# CarACESP32.net
KiCad netlist of a schematic drawn in Altium Designer
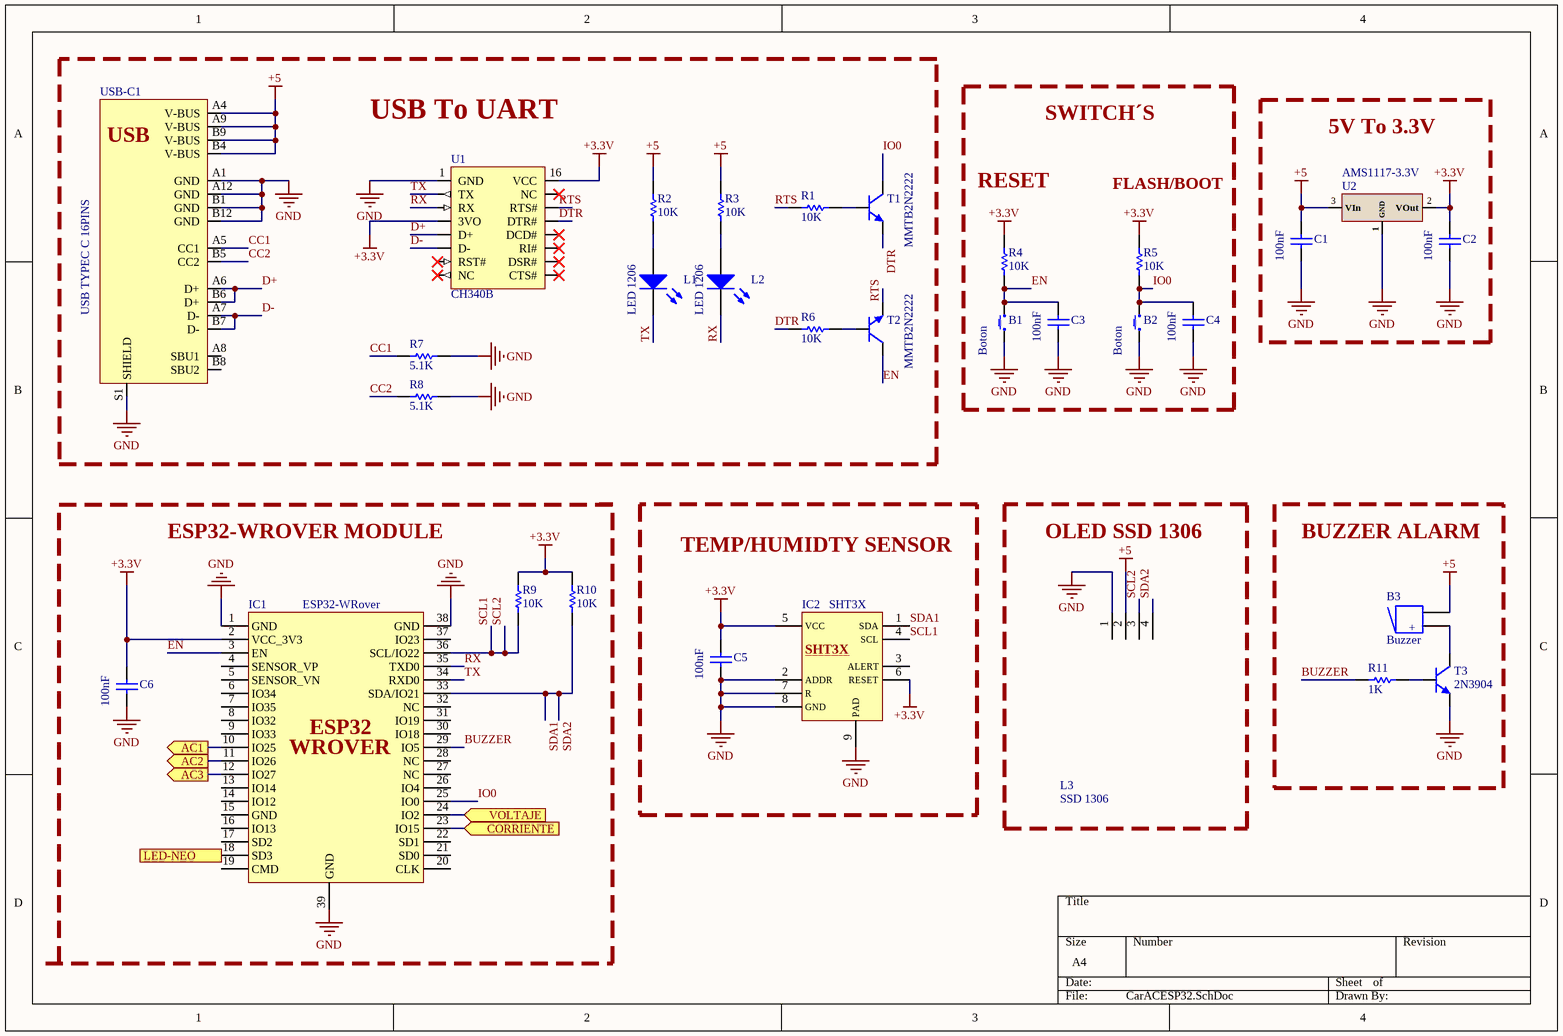
[diagram p0: CarACESP32.SchDoc]

(export (version "E")
  (design (tool "Eeschema 10.0.6"))
  (components
    (comp (ref "B1")
      (value "Boton")
      (footprint "Push Boton 2P C")
      (description "Micro Push TH")
      (libsource (lib "Switch & Relays FAE") (part "Push Boton 2 Pin TH"))
    )
    (comp (ref "B2")
      (value "Boton")
      (footprint "Push Boton 2P C")
      (description "Micro Push TH")
      (libsource (lib "Switch & Relays FAE") (part "Push Boton 2 Pin TH"))
    )
    (comp (ref "B3")
      (value "Buzzer")
      (footprint "Buzzer")
      (description "Active Sound")
      (libsource (lib "Mi Libreria") (part "Buzzer"))
    )
    (comp (ref "C1")
      (value "100nF")
      (footprint "Capacitor 1206")
      (description "Capacitor cerámico 1206 SMD")
      (libsource (lib "Mi Libreria") (part "Capacitor 1206"))
    )
    (comp (ref "C2")
      (value "100nF")
      (footprint "Capacitor 1206")
      (description "Capacitor cerámico 1206 SMD")
      (libsource (lib "Mi Libreria") (part "Capacitor 1206"))
    )
    (comp (ref "C3")
      (value "100nF")
      (footprint "Capacitor 1206")
      (description "Capacitor cerámico 1206 SMD")
      (libsource (lib "Mi Libreria") (part "Capacitor 1206"))
    )
    (comp (ref "C4")
      (value "100nF")
      (footprint "Capacitor 1206")
      (description "Capacitor cerámico 1206 SMD")
      (libsource (lib "Mi Libreria") (part "Capacitor 1206"))
    )
    (comp (ref "C5")
      (value "100nF")
      (footprint "Capacitor 1206")
      (description "Capacitor cerámico 1206 SMD")
      (libsource (lib "Mi Libreria") (part "Capacitor 1206"))
    )
    (comp (ref "C6")
      (value "100nF")
      (footprint "Capacitor 1206")
      (description "Capacitor cerámico 1206 SMD")
      (libsource (lib "Mi Libreria") (part "Capacitor 1206"))
    )
    (comp (ref "IC1")
      (value "ESP32-WRover")
      (footprint "ESP32-WROVER-B")
      (description "ESP32-WRover 39Pins")
      (libsource (lib "MyLabrary") (part "ESP32-WRover"))
    )
    (comp (ref "IC2") (value "SHT3X") (footprint "DFN-8_DD") (libsource (lib "MyLabrary") (part "SHT3X")))
    (comp (ref "L1")
      (value "LED 1206")
      (footprint "LED 1206 G")
      (description "LED SMD 1206")
      (libsource (lib "Led & Displays") (part "LED 1206"))
    )
    (comp (ref "L2")
      (value "LED 1206")
      (footprint "LED 1206 R")
      (description "LED SMD 1206")
      (libsource (lib "Led & Displays") (part "LED 1206"))
    )
    (comp (ref "L3")
      (value "SSD 1306")
      (footprint "OLEDSSD1306")
      (description "Pantalla OLED 124x64")
      (libsource (lib "MyLabrary") (part "SSD 1306"))
    )
    (comp (ref "R1")
      (value "10K")
      (footprint "Resistencia 1206")
      (description "Resistencia SMD 1206")
      (libsource (lib "Mi Libreria") (part "Resistencia SMD 1206"))
    )
    (comp (ref "R2")
      (value "10K")
      (footprint "Resistencia 1206")
      (description "Resistencia SMD 1206")
      (libsource (lib "Mi Libreria") (part "Resistencia SMD 1206"))
    )
    (comp (ref "R3")
      (value "10K")
      (footprint "Resistencia 1206")
      (description "Resistencia SMD 1206")
      (libsource (lib "Mi Libreria") (part "Resistencia SMD 1206"))
    )
    (comp (ref "R4")
      (value "10K")
      (footprint "Resistencia 1206")
      (description "Resistencia SMD 1206")
      (libsource (lib "Mi Libreria") (part "Resistencia SMD 1206"))
    )
    (comp (ref "R5")
      (value "10K")
      (footprint "Resistencia 1206")
      (description "Resistencia SMD 1206")
      (libsource (lib "Mi Libreria") (part "Resistencia SMD 1206"))
    )
    (comp (ref "R6")
      (value "10K")
      (footprint "Resistencia 1206")
      (description "Resistencia SMD 1206")
      (libsource (lib "Mi Libreria") (part "Resistencia SMD 1206"))
    )
    (comp (ref "R7")
      (value "5.1K")
      (footprint "Resistencia 1206")
      (description "Resistencia SMD 1206")
      (libsource (lib "Mi Libreria") (part "Resistencia SMD 1206"))
    )
    (comp (ref "R8")
      (value "5.1K")
      (footprint "Resistencia 1206")
      (description "Resistencia SMD 1206")
      (libsource (lib "Mi Libreria") (part "Resistencia SMD 1206"))
    )
    (comp (ref "R9")
      (value "10K")
      (footprint "Resistencia 1206")
      (description "Resistencia SMD 1206")
      (libsource (lib "Mi Libreria") (part "Resistencia SMD 1206"))
    )
    (comp (ref "R10")
      (value "10K")
      (footprint "Resistencia 1206")
      (description "Resistencia SMD 1206")
      (libsource (lib "Mi Libreria") (part "Resistencia SMD 1206"))
    )
    (comp (ref "R11")
      (value "1K")
      (footprint "Resistencia 1206")
      (description "Resistencia SMD 1206")
      (libsource (lib "Mi Libreria") (part "Resistencia SMD 1206"))
    )
    (comp (ref "T1")
      (value "MMTB2N2222")
      (footprint "SOT23_M")
      (libsource (lib "MyLabrary") (part "MMBT2N2222A"))
    )
    (comp (ref "T2")
      (value "MMTB2N2222")
      (footprint "SOT23_M")
      (libsource (lib "MyLabrary") (part "MMBT2N2222A"))
    )
    (comp (ref "T3") (value "2N3904") (footprint "NewTO-92A") (libsource (lib "MyLabrary") (part "2N3904")))
    (comp (ref "U1")
      (value "CH340B")
      (footprint "SOIC 16")
      (description "USB-Serial Converter")
      (libsource (lib "MyLabrary") (part "CH340B"))
    )
    (comp (ref "U2")
      (value "AMS1117-3.3V")
      (footprint "SOT 223")
      (description "Regulador Lineal de Voltaje")
      (libsource (lib "Mi Libreria") (part "AMS1117"))
    )
    (comp (ref "USB-C1")
      (value "USB TYPEC C 16PINS")
      (footprint "USB-TYPE_C-16")
      (description "USB Type C 16 Pins")
      (libsource (lib "MyLabrary") (part "USB TYPEC C 16PINS"))
    )
  )
  (nets
    (net (code "1") (name "+3.3V") (class "Default")
      (node (ref "C2") (pin "2") (pinfunction "2_2") (pintype "passive"))
      (node (ref "C5") (pin "2") (pinfunction "2_2") (pintype "passive"))
      (node (ref "C6") (pin "2") (pinfunction "2_2") (pintype "passive"))
      (node (ref "IC1") (pin "2") (pinfunction "VCC_3V3_2") (pintype "passive"))
      (node (ref "IC2") (pin "5") (pinfunction "VCC_5") (pintype "passive"))
      (node (ref "IC2") (pin "6") (pinfunction "RESET_6") (pintype "passive"))
      (node (ref "R10") (pin "2") (pinfunction "B_2") (pintype "passive"))
      (node (ref "R4") (pin "2") (pinfunction "B_2") (pintype "passive"))
      (node (ref "R5") (pin "2") (pinfunction "B_2") (pintype "passive"))
      (node (ref "R9") (pin "2") (pinfunction "B_2") (pintype "passive"))
      (node (ref "U1") (pin "16") (pinfunction "VCC_16") (pintype "passive"))
      (node (ref "U1") (pin "4") (pinfunction "3VO_4") (pintype "passive"))
      (node (ref "U2") (pin "2") (pinfunction "VOut_2") (pintype "passive"))
    )
    (net (code "2") (name "+5") (class "Default")
      (node (ref "B3") (pin "2") (pinfunction "2_2") (pintype "passive"))
      (node (ref "C1") (pin "2") (pinfunction "2_2") (pintype "passive"))
      (node (ref "L3") (pin "2") (pinfunction "2_2") (pintype "passive"))
      (node (ref "R2") (pin "2") (pinfunction "B_2") (pintype "passive"))
      (node (ref "R3") (pin "2") (pinfunction "B_2") (pintype "passive"))
      (node (ref "U2") (pin "3") (pinfunction "VIn_3") (pintype "passive"))
      (node (ref "USB-C1") (pin "A4") (pinfunction "V-BUS_A4") (pintype "passive"))
      (node (ref "USB-C1") (pin "A9") (pinfunction "V-BUS_A9") (pintype "passive"))
      (node (ref "USB-C1") (pin "B4") (pinfunction "V-BUS_B4") (pintype "passive"))
      (node (ref "USB-C1") (pin "B9") (pinfunction "V-BUS_B9") (pintype "passive"))
    )
    (net (code "3") (name "/AC1") (class "Default")
      (node (ref "IC1") (pin "10") (pinfunction "IO25_10") (pintype "passive"))
    )
    (net (code "4") (name "/AC2") (class "Default")
      (node (ref "IC1") (pin "11") (pinfunction "IO26_11") (pintype "passive"))
    )
    (net (code "5") (name "/AC3") (class "Default")
      (node (ref "IC1") (pin "12") (pinfunction "IO27_12") (pintype "passive"))
    )
    (net (code "6") (name "/BUZZER") (class "Default")
      (node (ref "IC1") (pin "29") (pinfunction "IO5_29") (pintype "passive"))
      (node (ref "R11") (pin "2") (pinfunction "B_2") (pintype "passive"))
    )
    (net (code "7") (name "/CC1") (class "Default")
      (node (ref "R7") (pin "2") (pinfunction "B_2") (pintype "passive"))
      (node (ref "USB-C1") (pin "A5") (pinfunction "CC1_A5") (pintype "passive"))
    )
    (net (code "8") (name "/CC2") (class "Default")
      (node (ref "R8") (pin "2") (pinfunction "B_2") (pintype "passive"))
      (node (ref "USB-C1") (pin "B5") (pinfunction "CC2_B5") (pintype "passive"))
    )
    (net (code "9") (name "/CORRIENTE") (class "Default")
      (node (ref "IC1") (pin "23") (pinfunction "IO15_23") (pintype "passive"))
    )
    (net (code "10") (name "/D+") (class "Default")
      (node (ref "U1") (pin "5") (pinfunction "D+_5") (pintype "passive"))
      (node (ref "USB-C1") (pin "A6") (pinfunction "D+_A6") (pintype "passive"))
      (node (ref "USB-C1") (pin "B6") (pinfunction "D+_B6") (pintype "passive"))
    )
    (net (code "11") (name "/D-") (class "Default")
      (node (ref "U1") (pin "6") (pinfunction "D-_6") (pintype "passive"))
      (node (ref "USB-C1") (pin "A7") (pinfunction "D-_A7") (pintype "passive"))
      (node (ref "USB-C1") (pin "B7") (pinfunction "D-_B7") (pintype "passive"))
    )
    (net (code "12") (name "/DTR") (class "Default")
      (node (ref "R6") (pin "2") (pinfunction "B_2") (pintype "passive"))
      (node (ref "T1") (pin "2") (pinfunction "E_2") (pintype "passive"))
      (node (ref "U1") (pin "13") (pinfunction "DTR#_13") (pintype "passive"))
    )
    (net (code "13") (name "/EN") (class "Default")
      (node (ref "B1") (pin "2") (pinfunction "28_2") (pintype "passive"))
      (node (ref "C3") (pin "2") (pinfunction "2_2") (pintype "passive"))
      (node (ref "IC1") (pin "3") (pinfunction "EN_3") (pintype "passive"))
      (node (ref "R4") (pin "1") (pinfunction "A_1") (pintype "passive"))
      (node (ref "T2") (pin "3") (pinfunction "C_3") (pintype "passive"))
    )
    (net (code "14") (name "/IO0") (class "Default")
      (node (ref "B2") (pin "2") (pinfunction "28_2") (pintype "passive"))
      (node (ref "C4") (pin "2") (pinfunction "2_2") (pintype "passive"))
      (node (ref "IC1") (pin "25") (pinfunction "IO0_25") (pintype "passive"))
      (node (ref "R5") (pin "1") (pinfunction "A_1") (pintype "passive"))
      (node (ref "T1") (pin "3") (pinfunction "C_3") (pintype "passive"))
    )
    (net (code "15") (name "/LED-NEO") (class "Default")
      (node (ref "IC1") (pin "18") (pinfunction "SD3_18") (pintype "passive"))
    )
    (net (code "16") (name "/RTS") (class "Default")
      (node (ref "R1") (pin "2") (pinfunction "B_2") (pintype "passive"))
      (node (ref "T2") (pin "2") (pinfunction "E_2") (pintype "passive"))
      (node (ref "U1") (pin "14") (pinfunction "RTS#_14") (pintype "passive"))
    )
    (net (code "17") (name "/RX") (class "Default")
      (node (ref "IC1") (pin "35") (pinfunction "TXD0_35") (pintype "passive"))
      (node (ref "L2") (pin "2") (pinfunction "K_2") (pintype "passive"))
      (node (ref "U1") (pin "3") (pinfunction "RX_3") (pintype "input"))
    )
    (net (code "18") (name "/SCL1") (class "Default")
      (node (ref "IC1") (pin "36") (pinfunction "SCL/IO22_36") (pintype "passive"))
      (node (ref "IC2") (pin "4") (pinfunction "SCL_4") (pintype "passive"))
      (node (ref "L3") (pin "3") (pinfunction "3_3") (pintype "passive"))
      (node (ref "R9") (pin "1") (pinfunction "A_1") (pintype "passive"))
    )
    (net (code "19") (name "/SDA1") (class "Default")
      (node (ref "IC1") (pin "33") (pinfunction "SDA/IO21_33") (pintype "passive"))
      (node (ref "IC2") (pin "1") (pinfunction "SDA_1") (pintype "passive"))
      (node (ref "L3") (pin "4") (pinfunction "4_4") (pintype "passive"))
      (node (ref "R10") (pin "1") (pinfunction "A_1") (pintype "passive"))
    )
    (net (code "20") (name "/TX") (class "Default")
      (node (ref "IC1") (pin "34") (pinfunction "RXD0_34") (pintype "passive"))
      (node (ref "L1") (pin "2") (pinfunction "K_2") (pintype "passive"))
      (node (ref "U1") (pin "2") (pinfunction "TX_2") (pintype "output"))
    )
    (net (code "21") (name "/VOLTAJE") (class "Default")
      (node (ref "IC1") (pin "24") (pinfunction "IO2_24") (pintype "passive"))
    )
    (net (code "22") (name "GND") (class "Default")
      (node (ref "B1") (pin "1") (pinfunction "27_1") (pintype "passive"))
      (node (ref "B2") (pin "1") (pinfunction "27_1") (pintype "passive"))
      (node (ref "C1") (pin "1") (pinfunction "1_1") (pintype "passive"))
      (node (ref "C2") (pin "1") (pinfunction "1_1") (pintype "passive"))
      (node (ref "C3") (pin "1") (pinfunction "1_1") (pintype "passive"))
      (node (ref "C4") (pin "1") (pinfunction "1_1") (pintype "passive"))
      (node (ref "C5") (pin "1") (pinfunction "1_1") (pintype "passive"))
      (node (ref "C6") (pin "1") (pinfunction "1_1") (pintype "passive"))
      (node (ref "IC1") (pin "1") (pinfunction "GND_1") (pintype "passive"))
      (node (ref "IC1") (pin "38") (pinfunction "GND_38") (pintype "passive"))
      (node (ref "IC1") (pin "39") (pinfunction "GND_39") (pintype "passive"))
      (node (ref "IC2") (pin "2") (pinfunction "ADDR_2") (pintype "passive"))
      (node (ref "IC2") (pin "7") (pinfunction "R_7") (pintype "passive"))
      (node (ref "IC2") (pin "8") (pinfunction "GND_8") (pintype "passive"))
      (node (ref "IC2") (pin "9") (pinfunction "PAD_9") (pintype "passive"))
      (node (ref "L3") (pin "1") (pinfunction "1_1") (pintype "passive"))
      (node (ref "R7") (pin "1") (pinfunction "A_1") (pintype "passive"))
      (node (ref "R8") (pin "1") (pinfunction "A_1") (pintype "passive"))
      (node (ref "T3") (pin "1") (pinfunction "E_1") (pintype "passive"))
      (node (ref "U1") (pin "1") (pinfunction "GND_1") (pintype "passive"))
      (node (ref "U2") (pin "1") (pinfunction "GND_1") (pintype "passive"))
      (node (ref "USB-C1") (pin "A1") (pinfunction "GND_A1") (pintype "passive"))
      (node (ref "USB-C1") (pin "A12") (pinfunction "GND_A12") (pintype "passive"))
      (node (ref "USB-C1") (pin "B1") (pinfunction "GND_B1") (pintype "passive"))
      (node (ref "USB-C1") (pin "B12") (pinfunction "GND_B12") (pintype "passive"))
      (node (ref "USB-C1") (pin "S1") (pinfunction "SHIELD_S1") (pintype "passive"))
    )
    (net (code "23") (name "Net-(L1-A)") (class "Default")
      (node (ref "L1") (pin "1") (pinfunction "A_1") (pintype "passive"))
      (node (ref "R2") (pin "1") (pinfunction "A_1") (pintype "passive"))
    )
    (net (code "24") (name "Net-(L2-A)") (class "Default")
      (node (ref "L2") (pin "1") (pinfunction "A_1") (pintype "passive"))
      (node (ref "R3") (pin "1") (pinfunction "A_1") (pintype "passive"))
    )
    (net (code "25") (name "Net-(R1-A)") (class "Default")
      (node (ref "R1") (pin "1") (pinfunction "A_1") (pintype "passive"))
      (node (ref "T1") (pin "1") (pinfunction "B_1") (pintype "passive"))
    )
    (net (code "26") (name "Net-(R6-A)") (class "Default")
      (node (ref "R6") (pin "1") (pinfunction "A_1") (pintype "passive"))
      (node (ref "T2") (pin "1") (pinfunction "B_1") (pintype "passive"))
    )
    (net (code "27") (name "Net-(R11-A)") (class "Default")
      (node (ref "R11") (pin "1") (pinfunction "A_1") (pintype "passive"))
      (node (ref "T3") (pin "2") (pinfunction "B_2") (pintype "passive"))
    )
    (net (code "28") (name "Net-(T3-C)") (class "Default")
      (node (ref "B3") (pin "1") (pinfunction "1_1") (pintype "passive"))
      (node (ref "T3") (pin "3") (pinfunction "C_3") (pintype "passive"))
    )
    (net (code "29") (name "unconnected-(IC1-CLK-Pad20)") (class "Default")
      (node (ref "IC1") (pin "20") (pinfunction "CLK_20") (pintype "passive"))
    )
    (net (code "30") (name "unconnected-(IC1-CMD-Pad19)") (class "Default")
      (node (ref "IC1") (pin "19") (pinfunction "CMD_19") (pintype "passive"))
    )
    (net (code "31") (name "unconnected-(IC1-GND-Pad15)") (class "Default")
      (node (ref "IC1") (pin "15") (pinfunction "GND_15") (pintype "passive"))
    )
    (net (code "32") (name "unconnected-(IC1-IO4-Pad26)") (class "Default")
      (node (ref "IC1") (pin "26") (pinfunction "IO4_26") (pintype "passive"))
    )
    (net (code "33") (name "unconnected-(IC1-IO12-Pad14)") (class "Default")
      (node (ref "IC1") (pin "14") (pinfunction "IO12_14") (pintype "passive"))
    )
    (net (code "34") (name "unconnected-(IC1-IO13-Pad16)") (class "Default")
      (node (ref "IC1") (pin "16") (pinfunction "IO13_16") (pintype "passive"))
    )
    (net (code "35") (name "unconnected-(IC1-IO14-Pad13)") (class "Default")
      (node (ref "IC1") (pin "13") (pinfunction "IO14_13") (pintype "passive"))
    )
    (net (code "36") (name "unconnected-(IC1-IO18-Pad30)") (class "Default")
      (node (ref "IC1") (pin "30") (pinfunction "IO18_30") (pintype "passive"))
    )
    (net (code "37") (name "unconnected-(IC1-IO19-Pad31)") (class "Default")
      (node (ref "IC1") (pin "31") (pinfunction "IO19_31") (pintype "passive"))
    )
    (net (code "38") (name "unconnected-(IC1-IO23-Pad37)") (class "Default")
      (node (ref "IC1") (pin "37") (pinfunction "IO23_37") (pintype "passive"))
    )
    (net (code "39") (name "unconnected-(IC1-IO32-Pad8)") (class "Default")
      (node (ref "IC1") (pin "8") (pinfunction "IO32_8") (pintype "passive"))
    )
    (net (code "40") (name "unconnected-(IC1-IO33-Pad9)") (class "Default")
      (node (ref "IC1") (pin "9") (pinfunction "IO33_9") (pintype "passive"))
    )
    (net (code "41") (name "unconnected-(IC1-IO34-Pad6)") (class "Default")
      (node (ref "IC1") (pin "6") (pinfunction "IO34_6") (pintype "passive"))
    )
    (net (code "42") (name "unconnected-(IC1-IO35-Pad7)") (class "Default")
      (node (ref "IC1") (pin "7") (pinfunction "IO35_7") (pintype "passive"))
    )
    (net (code "43") (name "unconnected-(IC1-NC-Pad27)") (class "Default")
      (node (ref "IC1") (pin "27") (pinfunction "NC_27") (pintype "passive"))
    )
    (net (code "44") (name "unconnected-(IC1-NC-Pad28)") (class "Default")
      (node (ref "IC1") (pin "28") (pinfunction "NC_28") (pintype "passive"))
    )
    (net (code "45") (name "unconnected-(IC1-NC-Pad32)") (class "Default")
      (node (ref "IC1") (pin "32") (pinfunction "NC_32") (pintype "passive"))
    )
    (net (code "46") (name "unconnected-(IC1-SD0-Pad21)") (class "Default")
      (node (ref "IC1") (pin "21") (pinfunction "SD0_21") (pintype "passive"))
    )
    (net (code "47") (name "unconnected-(IC1-SD1-Pad22)") (class "Default")
      (node (ref "IC1") (pin "22") (pinfunction "SD1_22") (pintype "passive"))
    )
    (net (code "48") (name "unconnected-(IC1-SD2-Pad17)") (class "Default")
      (node (ref "IC1") (pin "17") (pinfunction "SD2_17") (pintype "passive"))
    )
    (net (code "49") (name "unconnected-(IC1-SENSOR_VN-Pad5)") (class "Default")
      (node (ref "IC1") (pin "5") (pinfunction "SENSOR_VN_5") (pintype "passive"))
    )
    (net (code "50") (name "unconnected-(IC1-SENSOR_VP-Pad4)") (class "Default")
      (node (ref "IC1") (pin "4") (pinfunction "SENSOR_VP_4") (pintype "passive"))
    )
    (net (code "51") (name "unconnected-(IC2-ALERT-Pad3)") (class "Default")
      (node (ref "IC2") (pin "3") (pinfunction "ALERT_3") (pintype "passive"))
    )
    (net (code "52") (name "unconnected-(U1-CTS#-Pad9)") (class "Default")
      (node (ref "U1") (pin "9") (pinfunction "CTS#_9") (pintype "passive+no_connect"))
    )
    (net (code "53") (name "unconnected-(U1-DCD#-Pad12)") (class "Default")
      (node (ref "U1") (pin "12") (pinfunction "DCD#_12") (pintype "passive+no_connect"))
    )
    (net (code "54") (name "unconnected-(U1-DSR#-Pad10)") (class "Default")
      (node (ref "U1") (pin "10") (pinfunction "DSR#_10") (pintype "passive+no_connect"))
    )
    (net (code "55") (name "unconnected-(U1-NC-Pad8)") (class "Default")
      (node (ref "U1") (pin "8") (pinfunction "NC_8") (pintype "output+no_connect"))
    )
    (net (code "56") (name "unconnected-(U1-NC-Pad15)") (class "Default")
      (node (ref "U1") (pin "15") (pinfunction "NC_15") (pintype "passive+no_connect"))
    )
    (net (code "57") (name "unconnected-(U1-RI#-Pad11)") (class "Default")
      (node (ref "U1") (pin "11") (pinfunction "RI#_11") (pintype "passive+no_connect"))
    )
    (net (code "58") (name "unconnected-(U1-RST#-Pad7)") (class "Default")
      (node (ref "U1") (pin "7") (pinfunction "RST#_7") (pintype "input+no_connect"))
    )
    (net (code "59") (name "unconnected-(USB-C1-SBU1-PadA8)") (class "Default")
      (node (ref "USB-C1") (pin "A8") (pinfunction "SBU1_A8") (pintype "passive"))
    )
    (net (code "60") (name "unconnected-(USB-C1-SBU2-PadB8)") (class "Default")
      (node (ref "USB-C1") (pin "B8") (pinfunction "SBU2_B8") (pintype "passive"))
    )
  )
)
